# digitalcontrol.net
KiCad netlist of a schematic drawn in EAGLE
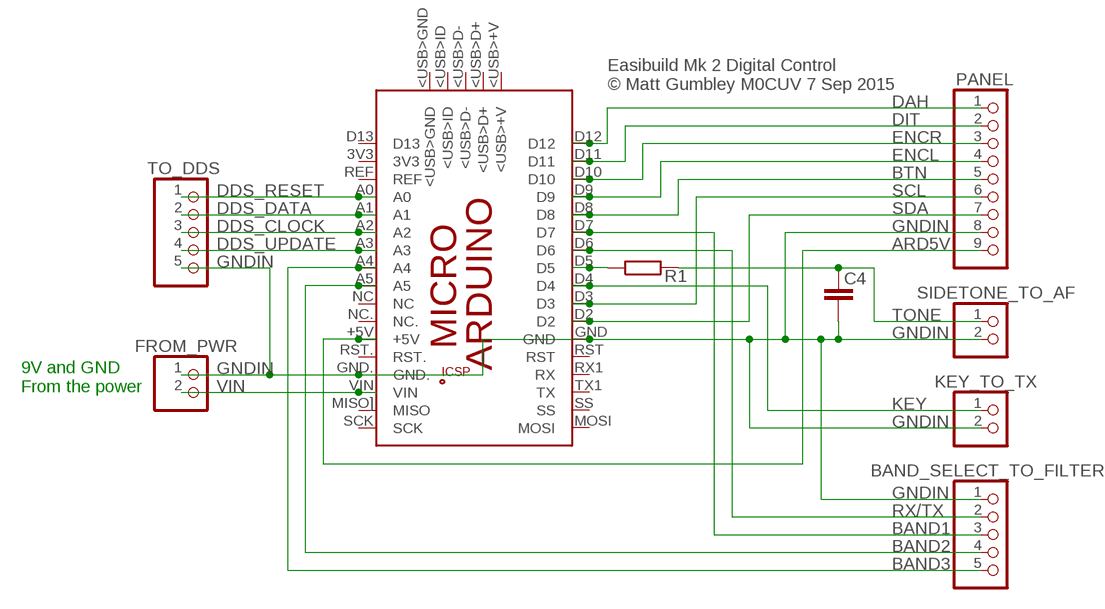
[diagram p0: schematic, sheet 1]

(export (version "E")
  (design (tool "Eeschema 10.0.6"))
  (components
    (comp (ref "BAND_SELECT_TO_FILTERS")
      (value "PINHD-1X5")
      (footprint "eagle-import:1X05")
      (libsource (lib "eagle-import") (part "PINHD-1X5"))
    )
    (comp (ref "C4")
      (value "C-EU050-025X075")
      (footprint "eagle-import:C050-025X075")
      (libsource (lib "eagle-import") (part "C-EU050-025X075"))
    )
    (comp (ref "FROM_PWR")
      (value "PINHD-1X2")
      (footprint "eagle-import:1X02")
      (libsource (lib "eagle-import") (part "PINHD-1X2"))
    )
    (comp (ref "KEY_TO_TX")
      (value "PINHD-1X2")
      (footprint "eagle-import:1X02")
      (libsource (lib "eagle-import") (part "PINHD-1X2"))
    )
    (comp (ref "PANEL")
      (value "PINHD-1X9")
      (footprint "eagle-import:1X09")
      (libsource (lib "eagle-import") (part "PINHD-1X9"))
    )
    (comp (ref "PCB1")
      (value "ARDUINO_MICRO")
      (footprint "eagle-import:ARDUINO_MICRO")
      (libsource (lib "eagle-import") (part "ARDUINO_MICRO"))
    )
    (comp (ref "R1")
      (value "R-EU_0204/5")
      (footprint "eagle-import:0204_5")
      (libsource (lib "eagle-import") (part "R-EU_0204/5"))
    )
    (comp (ref "SIDETONE_TO_AF")
      (value "PINHD-1X2")
      (footprint "eagle-import:1X02")
      (libsource (lib "eagle-import") (part "PINHD-1X2"))
    )
    (comp (ref "TO_DDS")
      (value "PINHD-1X5")
      (footprint "eagle-import:1X05")
      (libsource (lib "eagle-import") (part "PINHD-1X5"))
    )
  )
  (nets
    (net (code "1") (name "/ARD5V") (class "Default")
      (node (ref "PANEL") (pin "9") (pinfunction "9_9") (pintype "passive"))
      (node (ref "PCB1") (pin "+5V") (pinfunction "+5V_+5V") (pintype "bidirectional"))
    )
    (net (code "2") (name "/BAND1") (class "Default")
      (node (ref "BAND_SELECT_TO_FILTERS") (pin "3") (pinfunction "3_3") (pintype "passive"))
      (node (ref "PCB1") (pin "D7") (pinfunction "D7_D7") (pintype "bidirectional"))
    )
    (net (code "3") (name "/BAND2") (class "Default")
      (node (ref "BAND_SELECT_TO_FILTERS") (pin "4") (pinfunction "4_4") (pintype "passive"))
      (node (ref "PCB1") (pin "A5") (pinfunction "A5_A5") (pintype "bidirectional"))
    )
    (net (code "4") (name "/BAND3") (class "Default")
      (node (ref "BAND_SELECT_TO_FILTERS") (pin "5") (pinfunction "5_5") (pintype "passive"))
      (node (ref "PCB1") (pin "A4") (pinfunction "A4_A4") (pintype "bidirectional"))
    )
    (net (code "5") (name "/BTN") (class "Default")
      (node (ref "PANEL") (pin "5") (pinfunction "5_5") (pintype "passive"))
      (node (ref "PCB1") (pin "D8") (pinfunction "D8_D8") (pintype "bidirectional"))
    )
    (net (code "6") (name "/DAH") (class "Default")
      (node (ref "PANEL") (pin "1") (pinfunction "1_1") (pintype "passive"))
      (node (ref "PCB1") (pin "D12") (pinfunction "D12_D12") (pintype "bidirectional"))
    )
    (net (code "7") (name "/DDS_CLOCK") (class "Default")
      (node (ref "PCB1") (pin "A2") (pinfunction "A2_A2") (pintype "bidirectional"))
      (node (ref "TO_DDS") (pin "3") (pinfunction "3_3") (pintype "passive"))
    )
    (net (code "8") (name "/DDS_DATA") (class "Default")
      (node (ref "PCB1") (pin "A1") (pinfunction "A1_A1") (pintype "bidirectional"))
      (node (ref "TO_DDS") (pin "2") (pinfunction "2_2") (pintype "passive"))
    )
    (net (code "9") (name "/DDS_RESET") (class "Default")
      (node (ref "PCB1") (pin "A0") (pinfunction "A0_A0") (pintype "bidirectional"))
      (node (ref "TO_DDS") (pin "1") (pinfunction "1_1") (pintype "passive"))
    )
    (net (code "10") (name "/DDS_UPDATE") (class "Default")
      (node (ref "PCB1") (pin "A3") (pinfunction "A3_A3") (pintype "bidirectional"))
      (node (ref "TO_DDS") (pin "4") (pinfunction "4_4") (pintype "passive"))
    )
    (net (code "11") (name "/DIT") (class "Default")
      (node (ref "PANEL") (pin "2") (pinfunction "2_2") (pintype "passive"))
      (node (ref "PCB1") (pin "D11") (pinfunction "D11_D11") (pintype "bidirectional"))
    )
    (net (code "12") (name "/ENCL") (class "Default")
      (node (ref "PANEL") (pin "4") (pinfunction "4_4") (pintype "passive"))
      (node (ref "PCB1") (pin "D9") (pinfunction "D9_D9") (pintype "bidirectional"))
    )
    (net (code "13") (name "/ENCR") (class "Default")
      (node (ref "PANEL") (pin "3") (pinfunction "3_3") (pintype "passive"))
      (node (ref "PCB1") (pin "D10") (pinfunction "D10_D10") (pintype "bidirectional"))
    )
    (net (code "14") (name "/GNDIN") (class "Default")
      (node (ref "BAND_SELECT_TO_FILTERS") (pin "1") (pinfunction "1_1") (pintype "passive"))
      (node (ref "C4") (pin "2") (pinfunction "2_2") (pintype "passive"))
      (node (ref "FROM_PWR") (pin "1") (pinfunction "1_1") (pintype "passive"))
      (node (ref "KEY_TO_TX") (pin "2") (pinfunction "2_2") (pintype "passive"))
      (node (ref "PANEL") (pin "8") (pinfunction "8_8") (pintype "passive"))
      (node (ref "PCB1") (pin "GND") (pinfunction "GND_GND") (pintype "bidirectional"))
      (node (ref "PCB1") (pin "GND.") (pinfunction "GND._GND.") (pintype "bidirectional"))
      (node (ref "SIDETONE_TO_AF") (pin "2") (pinfunction "2_2") (pintype "passive"))
      (node (ref "TO_DDS") (pin "5") (pinfunction "5_5") (pintype "passive"))
    )
    (net (code "15") (name "/KEY") (class "Default")
      (node (ref "KEY_TO_TX") (pin "1") (pinfunction "1_1") (pintype "passive"))
      (node (ref "PCB1") (pin "D4") (pinfunction "D4_D4") (pintype "bidirectional"))
    )
    (net (code "16") (name "/RX{slash}TX") (class "Default")
      (node (ref "BAND_SELECT_TO_FILTERS") (pin "2") (pinfunction "2_2") (pintype "passive"))
      (node (ref "PCB1") (pin "D6") (pinfunction "D6_D6") (pintype "bidirectional"))
    )
    (net (code "17") (name "/SCL") (class "Default")
      (node (ref "PANEL") (pin "6") (pinfunction "6_6") (pintype "passive"))
      (node (ref "PCB1") (pin "D3") (pinfunction "D3_D3") (pintype "bidirectional"))
    )
    (net (code "18") (name "/SDA") (class "Default")
      (node (ref "PANEL") (pin "7") (pinfunction "7_7") (pintype "passive"))
      (node (ref "PCB1") (pin "D2") (pinfunction "D2_D2") (pintype "bidirectional"))
    )
    (net (code "19") (name "/TONE") (class "Default")
      (node (ref "C4") (pin "1") (pinfunction "1_1") (pintype "passive"))
      (node (ref "R1") (pin "2") (pinfunction "2_2") (pintype "passive"))
      (node (ref "SIDETONE_TO_AF") (pin "1") (pinfunction "1_1") (pintype "passive"))
    )
    (net (code "20") (name "/VIN") (class "Default")
      (node (ref "FROM_PWR") (pin "2") (pinfunction "2_2") (pintype "passive"))
      (node (ref "PCB1") (pin "VIN") (pinfunction "VIN_VIN") (pintype "bidirectional"))
    )
    (net (code "21") (name "Net-(PCB1-PadD5)") (class "Default")
      (node (ref "PCB1") (pin "D5") (pinfunction "D5_D5") (pintype "bidirectional"))
      (node (ref "R1") (pin "1") (pinfunction "1_1") (pintype "passive"))
    )
    (net (code "22") (name "unconnected-(PCB1-MISO-PadMISO])") (class "Default")
      (node (ref "PCB1") (pin "MISO]") (pinfunction "MISO_MISO]") (pintype "bidirectional"))
    )
    (net (code "23") (name "unconnected-(PCB1-Pad3V3)") (class "Default")
      (node (ref "PCB1") (pin "3V3") (pinfunction "3V3_3V3") (pintype "bidirectional"))
    )
    (net (code "24") (name "unconnected-(PCB1-Pad5V)") (class "Default")
      (node (ref "PCB1") (pin "5V") (pinfunction "5V_5V") (pintype "bidirectional"))
    )
    (net (code "25") (name "unconnected-(PCB1-Pad<USB>+V)") (class "Default")
      (node (ref "PCB1") (pin "<USB>+V") (pinfunction "<USB>+V_<USB>+V") (pintype "bidirectional"))
    )
    (net (code "26") (name "unconnected-(PCB1-Pad<USB>D+)") (class "Default")
      (node (ref "PCB1") (pin "<USB>D+") (pinfunction "<USB>D+_<USB>D+") (pintype "bidirectional"))
    )
    (net (code "27") (name "unconnected-(PCB1-Pad<USB>D-)") (class "Default")
      (node (ref "PCB1") (pin "<USB>D-") (pinfunction "<USB>D-_<USB>D-") (pintype "bidirectional"))
    )
    (net (code "28") (name "unconnected-(PCB1-Pad<USB>GND)") (class "Default")
      (node (ref "PCB1") (pin "<USB>GND") (pinfunction "<USB>GND_<USB>GND") (pintype "bidirectional"))
    )
    (net (code "29") (name "unconnected-(PCB1-Pad<USB>ID)") (class "Default")
      (node (ref "PCB1") (pin "<USB>ID") (pinfunction "<USB>ID_<USB>ID") (pintype "bidirectional"))
    )
    (net (code "30") (name "unconnected-(PCB1-PadD13)") (class "Default")
      (node (ref "PCB1") (pin "D13") (pinfunction "D13_D13") (pintype "bidirectional"))
    )
    (net (code "31") (name "unconnected-(PCB1-PadGND_)") (class "Default")
      (node (ref "PCB1") (pin "GND_") (pinfunction "GND__GND_") (pintype "bidirectional"))
    )
    (net (code "32") (name "unconnected-(PCB1-PadMISO.)") (class "Default")
      (node (ref "PCB1") (pin "MISO.") (pinfunction "MISO._MISO.") (pintype "bidirectional"))
    )
    (net (code "33") (name "unconnected-(PCB1-PadMOSI)") (class "Default")
      (node (ref "PCB1") (pin "MOSI") (pinfunction "MOSI_MOSI") (pintype "bidirectional"))
    )
    (net (code "34") (name "unconnected-(PCB1-PadMOSI.)") (class "Default")
      (node (ref "PCB1") (pin "MOSI.") (pinfunction "MOSI._MOSI.") (pintype "bidirectional"))
    )
    (net (code "35") (name "unconnected-(PCB1-PadNC)") (class "Default")
      (node (ref "PCB1") (pin "NC") (pinfunction "NC_NC") (pintype "bidirectional"))
    )
    (net (code "36") (name "unconnected-(PCB1-PadNC.)") (class "Default")
      (node (ref "PCB1") (pin "NC.") (pinfunction "NC._NC.") (pintype "bidirectional"))
    )
    (net (code "37") (name "unconnected-(PCB1-PadREF)") (class "Default")
      (node (ref "PCB1") (pin "REF") (pinfunction "REF_REF") (pintype "bidirectional"))
    )
    (net (code "38") (name "unconnected-(PCB1-PadRESET..)") (class "Default")
      (node (ref "PCB1") (pin "RESET..") (pinfunction "RESET.._RESET..") (pintype "bidirectional"))
    )
    (net (code "39") (name "unconnected-(PCB1-PadRST)") (class "Default")
      (node (ref "PCB1") (pin "RST") (pinfunction "RST_RST") (pintype "bidirectional"))
    )
    (net (code "40") (name "unconnected-(PCB1-PadRST.)") (class "Default")
      (node (ref "PCB1") (pin "RST.") (pinfunction "RST._RST.") (pintype "bidirectional"))
    )
    (net (code "41") (name "unconnected-(PCB1-PadSCK)") (class "Default")
      (node (ref "PCB1") (pin "SCK") (pinfunction "SCK_SCK") (pintype "bidirectional"))
    )
    (net (code "42") (name "unconnected-(PCB1-PadSCK.)") (class "Default")
      (node (ref "PCB1") (pin "SCK.") (pinfunction "SCK._SCK.") (pintype "bidirectional"))
    )
    (net (code "43") (name "unconnected-(PCB1-PadSS)") (class "Default")
      (node (ref "PCB1") (pin "SS") (pinfunction "SS_SS") (pintype "bidirectional"))
    )
    (net (code "44") (name "unconnected-(PCB1-RX-PadRX1)") (class "Default")
      (node (ref "PCB1") (pin "RX1") (pinfunction "RX_RX1") (pintype "bidirectional"))
    )
    (net (code "45") (name "unconnected-(PCB1-TX-PadTX1)") (class "Default")
      (node (ref "PCB1") (pin "TX1") (pinfunction "TX_TX1") (pintype "bidirectional"))
    )
  )
)
